# Cyber_VCM.net
KiCad netlist of a schematic drawn in Altium Designer
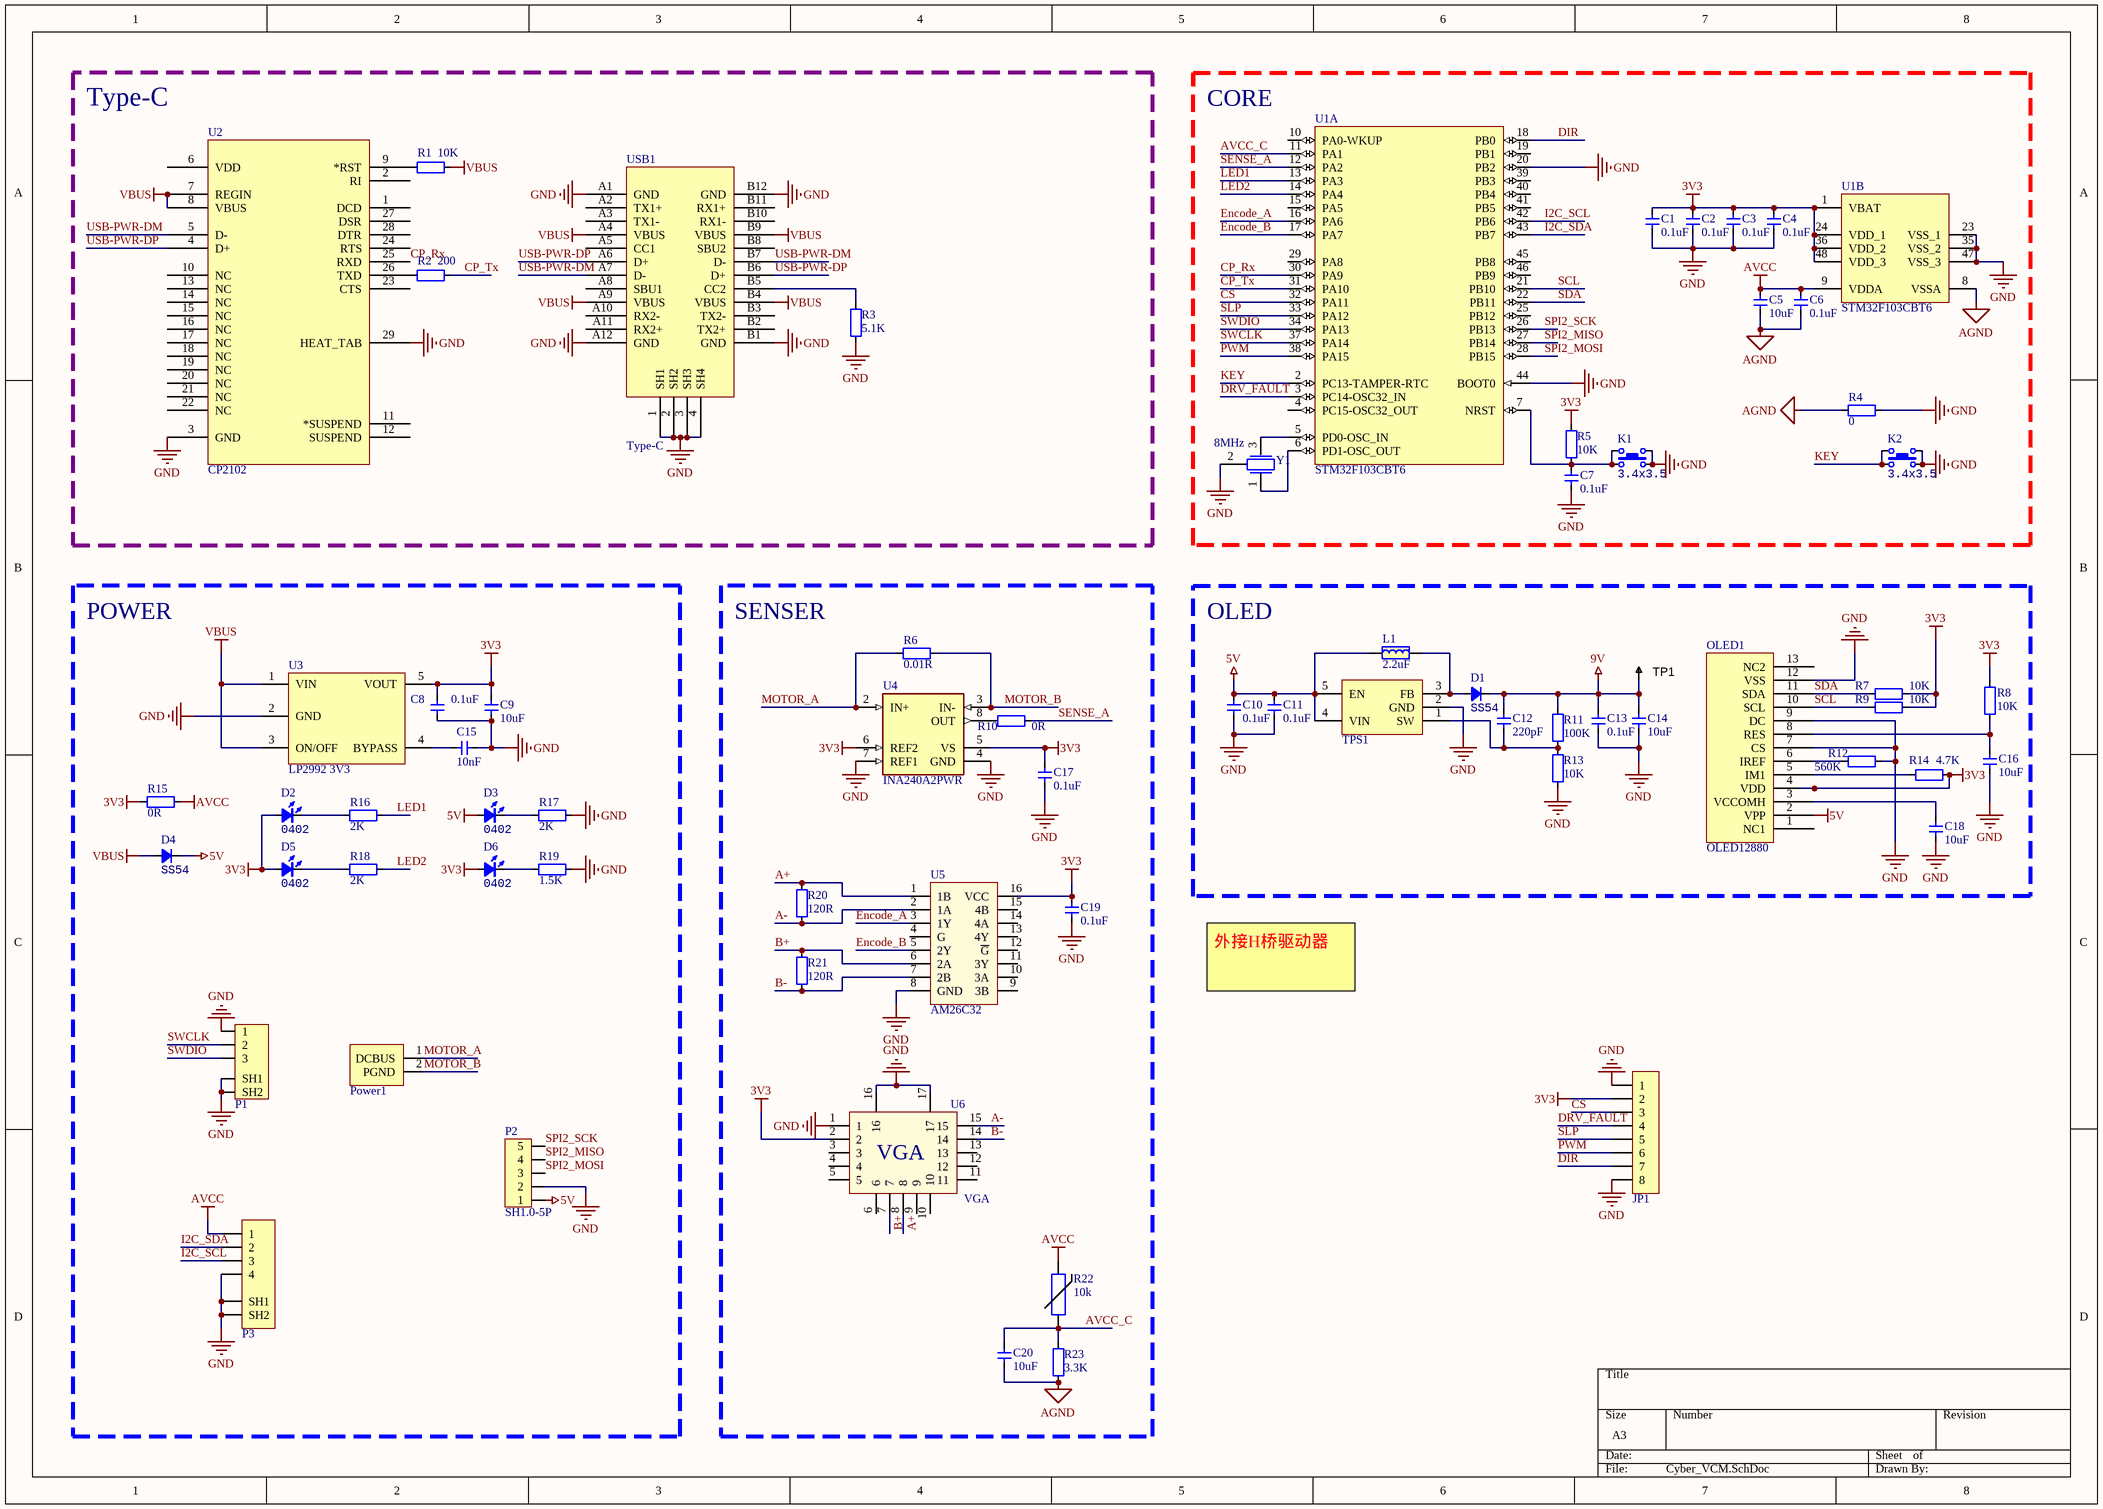
[diagram p0: Cyber_VCM.SchDoc]

(export (version "E")
  (design (tool "Eeschema 10.0.6"))
  (components
    (comp (ref "C1")
      (value "0.1uF")
      (footprint "CAP_0402")
      (description "Capacitor")
      (libsource (lib "Cyber_VCM") (part "电容-0402"))
    )
    (comp (ref "C2")
      (value "0.1uF")
      (footprint "CAP_0402")
      (description "Capacitor")
      (libsource (lib "Cyber_VCM") (part "电容-0402"))
    )
    (comp (ref "C3")
      (value "0.1uF")
      (footprint "CAP_0402")
      (description "Capacitor")
      (libsource (lib "Cyber_VCM") (part "电容-0402"))
    )
    (comp (ref "C4")
      (value "0.1uF")
      (footprint "CAP_0402")
      (description "Capacitor")
      (libsource (lib "Cyber_VCM") (part "电容-0402"))
    )
    (comp (ref "C5")
      (value "10uF")
      (footprint "CAP_0402")
      (description "Capacitor")
      (libsource (lib "Cyber_VCM") (part "电容-0402"))
    )
    (comp (ref "C6")
      (value "0.1uF")
      (footprint "CAP_0402")
      (description "Capacitor")
      (libsource (lib "Cyber_VCM") (part "电容-0402"))
    )
    (comp (ref "C7")
      (value "0.1uF")
      (footprint "CAP_0402")
      (description "Capacitor")
      (libsource (lib "MyPcbLib") (part "电容-0402"))
    )
    (comp (ref "C8")
      (value "0.1uF")
      (footprint "CAP_0402")
      (description "Capacitor")
      (libsource (lib "Cyber_VCM") (part "电容-0402"))
    )
    (comp (ref "C9")
      (value "10uF")
      (footprint "CAP_0402")
      (description "Capacitor")
      (libsource (lib "Cyber_VCM") (part "电容-0402"))
    )
    (comp (ref "C10")
      (value "0.1uF")
      (footprint "CAP_0402")
      (description "Capacitor")
      (libsource (lib "Serena-Ctrl") (part "电容-0402"))
    )
    (comp (ref "C11")
      (value "0.1uF")
      (footprint "CAP_0402")
      (description "Capacitor")
      (libsource (lib "Serena-Ctrl") (part "电容-0402"))
    )
    (comp (ref "C12")
      (value "220pF")
      (footprint "CAP_0402")
      (description "Capacitor")
      (libsource (lib "Serena-Ctrl") (part "电容-0402"))
    )
    (comp (ref "C13")
      (value "0.1uF")
      (footprint "0603-CAP")
      (description "Capacitor")
      (libsource (lib "Serena-Ctrl") (part "电容-0603"))
    )
    (comp (ref "C14")
      (value "10uF")
      (footprint "0603-CAP")
      (description "Capacitor")
      (libsource (lib "Serena-Ctrl") (part "电容-0603"))
    )
    (comp (ref "C15")
      (value "10nF")
      (footprint "CAP_0402")
      (description "Capacitor")
      (libsource (lib "Cyber_VCM") (part "电容-0402"))
    )
    (comp (ref "C16")
      (value "10uF")
      (footprint "CAP_0402")
      (description "Capacitor")
      (libsource (lib "MyPcbLib") (part "电容-0402"))
    )
    (comp (ref "C17")
      (value "0.1uF")
      (footprint "CAP_0402")
      (description "Capacitor")
      (libsource (lib "MyPcbLib") (part "电容-0402"))
    )
    (comp (ref "C18")
      (value "10uF")
      (footprint "CAP_0402")
      (description "Capacitor")
      (libsource (lib "MyPcbLib") (part "电容-0402"))
    )
    (comp (ref "C19")
      (value "0.1uF")
      (footprint "0603-CAP")
      (description "Capacitor")
      (libsource (lib "VCM_Ctrl") (part "电容-0603"))
    )
    (comp (ref "C20")
      (value "10uF")
      (footprint "CAP_0402")
      (description "Capacitor")
      (libsource (lib "MyPcbLib") (part "电容-0402"))
    )
    (comp (ref "D1")
      (value "SS54")
      (footprint "DO-214AC")
      (description "Diode")
      (libsource (lib "Serena-Ctrl") (part "Diode_SMA"))
    )
    (comp (ref "D2")
      (value "color?")
      (footprint "LED_0402_BLUE")
      (description "LED")
      (fields (field (name "TYPE") "0402"))
      (libsource (lib "Cyber_VCM") (part "LED_0402"))
    )
    (comp (ref "D3")
      (value "color?")
      (footprint "LED_0402_BLUE")
      (description "LED")
      (fields (field (name "TYPE") "0402"))
      (libsource (lib "Cyber_VCM") (part "LED_0402"))
    )
    (comp (ref "D4")
      (value "SS54")
      (footprint "DO-214AC")
      (description "Diode")
      (libsource (lib "Cyber_VCM") (part "Diode_SMA"))
    )
    (comp (ref "D5")
      (value "color?")
      (footprint "LED_0402_BLUE")
      (description "LED")
      (fields (field (name "TYPE") "0402"))
      (libsource (lib "Cyber_VCM") (part "LED_0402"))
    )
    (comp (ref "D6")
      (value "color?")
      (footprint "LED_0402_BLUE")
      (description "LED")
      (fields (field (name "TYPE") "0402"))
      (libsource (lib "Cyber_VCM") (part "LED_0402"))
    )
    (comp (ref "JP1")
      (value "HDR-1X8")
      (footprint "HDR2.54-M-LI-8P")
      (description "8P接插件")
      (fields (field (name "版权归属") "源创客"))
      (libsource (lib "Cyber_VCM") (part "Header 8"))
    )
    (comp (ref "K1")
      (value "3.4x3.5")
      (footprint "ButtonTACT_3.5*3.55_90")
      (description "Button")
      (fields (field (name "Comment") "TACT 4P"))
      (libsource (lib "KitSprout") (part "ButtonTACT"))
    )
    (comp (ref "K2")
      (value "3.4x3.5")
      (footprint "ButtonTACT_3.5*3.55_90")
      (description "Button")
      (fields (field (name "Comment") "TACT 4P"))
      (libsource (lib "KitSprout") (part "ButtonTACT"))
    )
    (comp (ref "L1")
      (value "2.2uF")
      (footprint "2520-L")
      (description "磁珠")
      (libsource (lib "Serena-Ctrl") (part "电感-0805"))
    )
    (comp (ref "OLED1")
      (value "OLED12880")
      (footprint "OLED12880")
      (description "12880寸OLED")
      (libsource (lib "Cyber_VCM") (part "OLED12880"))
    )
    (comp (ref "P1")
      (value "SH1.0-3P")
      (footprint "SH1.0-3P")
      (description "Header")
      (libsource (lib "Cyber_VCM") (part "SH1.0-3P"))
    )
    (comp (ref "P2") (value "SH1.0-5P") (footprint "SH1.0-5P") (libsource (lib "MyPcbLib") (part "SH1.0-5P")))
    (comp (ref "P3")
      (value "SH1.0-4P")
      (footprint "SH1.0-4P")
      (libsource (lib "Cyber_VCM") (part "SH1.0-4P"))
    )
    (comp (ref "Power1")
      (value "电源")
      (footprint "TX60电源")
      (description "12~24VDC电源")
      (libsource (lib "Cyber_VCM") (part "电源"))
    )
    (comp (ref "R1")
      (value "10K")
      (footprint "RES_0402")
      (description "Resistor")
      (libsource (lib "MyPcbLib") (part "电阻-0402"))
    )
    (comp (ref "R2")
      (value "200")
      (footprint "RES_0402")
      (description "Resistor")
      (libsource (lib "MyPcbLib") (part "电阻-0402"))
    )
    (comp (ref "R3")
      (value "5.1K")
      (footprint "RES_0402")
      (description "Resistor")
      (libsource (lib "") (part "电阻-0402_3"))
    )
    (comp (ref "R4")
      (value "0")
      (footprint "RES_0402")
      (description "Resistor")
      (libsource (lib "Cyber_VCM") (part "电阻-0402"))
    )
    (comp (ref "R5")
      (value "10K")
      (footprint "RES_0402")
      (description "Resistor")
      (libsource (lib "") (part "电阻-0402_1"))
    )
    (comp (ref "R6")
      (value "0.01R")
      (footprint "1206-RES")
      (description "Resistor")
      (libsource (lib "MyPcbLib") (part "电阻-1206"))
    )
    (comp (ref "R7")
      (value "10K")
      (footprint "RES_0402")
      (description "Resistor")
      (libsource (lib "VectorController") (part "电阻-0402"))
    )
    (comp (ref "R8")
      (value "10K")
      (footprint "RES_0402")
      (description "Resistor")
      (libsource (lib "") (part "电阻-0402_1"))
    )
    (comp (ref "R9")
      (value "10K")
      (footprint "RES_0402")
      (description "Resistor")
      (libsource (lib "VectorController") (part "电阻-0402"))
    )
    (comp (ref "R10")
      (value "0R")
      (footprint "RES_0402")
      (description "Resistor")
      (libsource (lib "Cyber_VCM") (part "电阻-0402"))
    )
    (comp (ref "R11")
      (value "100K")
      (footprint "RES_0402")
      (description "Resistor")
      (libsource (lib "Serena-Ctrl") (part "电阻-0402"))
    )
    (comp (ref "R12")
      (value "560K")
      (footprint "RES_0402")
      (description "Resistor")
      (libsource (lib "") (part "电阻-0402_2"))
    )
    (comp (ref "R13")
      (value "10K")
      (footprint "RES_0402")
      (description "Resistor")
      (libsource (lib "Serena-Ctrl") (part "电阻-0402"))
    )
    (comp (ref "R14")
      (value "4.7K")
      (footprint "RES_0402")
      (description "Resistor")
      (libsource (lib "") (part "电阻-0402_2"))
    )
    (comp (ref "R15")
      (value "0R")
      (footprint "RES_0402")
      (description "Resistor")
      (libsource (lib "MyPcbLib") (part "电阻-0402"))
    )
    (comp (ref "R16")
      (value "2K")
      (footprint "RES_0402")
      (description "Resistor")
      (libsource (lib "Cyber_VCM") (part "电阻-0402"))
    )
    (comp (ref "R17")
      (value "2K")
      (footprint "RES_0402")
      (description "Resistor")
      (libsource (lib "Cyber_VCM") (part "电阻-0402"))
    )
    (comp (ref "R18")
      (value "2K")
      (footprint "RES_0402")
      (description "Resistor")
      (libsource (lib "Cyber_VCM") (part "电阻-0402"))
    )
    (comp (ref "R19")
      (value "1.5K")
      (footprint "RES_0402")
      (description "Resistor")
      (libsource (lib "Cyber_VCM") (part "电阻-0402"))
    )
    (comp (ref "R20")
      (value "120R")
      (footprint "RES_0603")
      (description "Resistor")
      (libsource (lib "Ctrl_FOC") (part "电阻-0603"))
    )
    (comp (ref "R21")
      (value "120R")
      (footprint "RES_0603")
      (description "Resistor")
      (libsource (lib "Ctrl_FOC") (part "电阻-0603"))
    )
    (comp (ref "R22")
      (value "10k")
      (footprint "RES_0402")
      (description "THERMISTOR 10K OHM NTC 0402 SMD")
      (fields (field (name "Comment") "NCP15XH103F03RC"))
      (libsource (lib "MyPcbLib") (part "NCP15XH103F03RC"))
    )
    (comp (ref "R23")
      (value "3.3K")
      (footprint "RES_0402")
      (description "Resistor")
      (libsource (lib "") (part "电阻-0402_1"))
    )
    (comp (ref "TP1")
      (value "TESTPOINT")
      (footprint "TP-R30")
      (description "SMD test pin")
      (libsource (lib "Serena-Ctrl") (part "TESTPOINT"))
    )
    (comp (ref "TPS1")
      (value "TPS61040DBV")
      (footprint "SOT23-5")
      (libsource (lib "Serena-Ctrl") (part "TPS61040DBV"))
    )
    (comp (ref "U1")
      (value "STM32F103CBT6")
      (footprint "LQFP-48")
      (libsource (lib "Cyber_VCM") (part "STM32F103CBT6"))
    )
    (comp (ref "U2")
      (value "CP2102")
      (footprint "QFN-28")
      (description "USB转TTL")
      (libsource (lib "Cyber_VCM") (part "CP2102"))
    )
    (comp (ref "U3")
      (value "LP2992 3V3")
      (footprint "SOT23-5")
      (description "LDO")
      (libsource (lib "Cyber_VCM") (part "LP2992"))
    )
    (comp (ref "U4")
      (value "INA240A2PWR")
      (footprint "SOP65 P640X120-8N")
      (fields (field (name "MF") "Texas Instruments"))
      (libsource (lib "mLib") (part "INA240A2PWR"))
    )
    (comp (ref "U5")
      (value "AM26C32")
      (footprint "SOP16")
      (description "AM26C32 Quadruple Differential Line Receiver")
      (libsource (lib "VCM_Ctrl") (part "AM26C32"))
    )
    (comp (ref "U6") (value "VGA") (footprint "VGA15A") (libsource (lib "VCM_Ctrl") (part "VGA")))
    (comp (ref "USB1")
      (value "Type-C")
      (footprint "Type-C-TOP")
      (libsource (lib "Cyber_VCM") (part "USB-Type-C-TOP"))
    )
    (comp (ref "Y1")
      (value "8MHz")
      (footprint "晶振-3P")
      (description "村田贴片")
      (libsource (lib "MyPcbLib") (part "晶振-3Pin"))
    )
  )
  (nets
    (net (code "1") (name "/A+") (class "Default")
      (node (ref "R20") (pin "2") (pinfunction "2_2") (pintype "passive"))
      (node (ref "U5") (pin "1") (pinfunction "1B_1") (pintype "passive"))
      (node (ref "U6") (pin "8") (pinfunction "8_8") (pintype "passive"))
    )
    (net (code "2") (name "/A-") (class "Default")
      (node (ref "R20") (pin "1") (pinfunction "1_1") (pintype "passive"))
      (node (ref "U5") (pin "2") (pinfunction "1A_2") (pintype "passive"))
      (node (ref "U6") (pin "15") (pinfunction "15_15") (pintype "passive"))
    )
    (net (code "3") (name "/AVCC_C") (class "Default")
      (node (ref "C20") (pin "2") (pinfunction "2_2") (pintype "passive"))
      (node (ref "R22") (pin "1") (pinfunction "0_1") (pintype "passive"))
      (node (ref "R23") (pin "2") (pinfunction "2_2") (pintype "passive"))
      (node (ref "U1") (pin "11") (pinfunction "PA1_11") (pintype "bidirectional"))
    )
    (net (code "4") (name "/B+") (class "Default")
      (node (ref "R21") (pin "2") (pinfunction "2_2") (pintype "passive"))
      (node (ref "U5") (pin "6") (pinfunction "2A_6") (pintype "passive"))
      (node (ref "U6") (pin "7") (pinfunction "7_7") (pintype "passive"))
    )
    (net (code "5") (name "/B-") (class "Default")
      (node (ref "R21") (pin "1") (pinfunction "1_1") (pintype "passive"))
      (node (ref "U5") (pin "7") (pinfunction "2B_7") (pintype "passive"))
      (node (ref "U6") (pin "14") (pinfunction "14_14") (pintype "passive"))
    )
    (net (code "6") (name "/CP_Rx") (class "Default")
      (node (ref "U1") (pin "30") (pinfunction "PA9_30") (pintype "bidirectional"))
      (node (ref "U2") (pin "25") (pinfunction "RXD_25") (pintype "passive"))
    )
    (net (code "7") (name "/CP_Tx") (class "Default")
      (node (ref "R2") (pin "1") (pinfunction "1_1") (pintype "passive"))
      (node (ref "U1") (pin "31") (pinfunction "PA10_31") (pintype "bidirectional"))
    )
    (net (code "8") (name "/CS") (class "Default")
      (node (ref "JP1") (pin "3") (pinfunction "3_3") (pintype "passive"))
      (node (ref "U1") (pin "32") (pinfunction "PA11_32") (pintype "bidirectional"))
    )
    (net (code "9") (name "/DIR") (class "Default")
      (node (ref "JP1") (pin "7") (pinfunction "7_7") (pintype "passive"))
      (node (ref "U1") (pin "18") (pinfunction "PB0_18") (pintype "bidirectional"))
    )
    (net (code "10") (name "/DRV_FAULT") (class "Default")
      (node (ref "JP1") (pin "4") (pinfunction "4_4") (pintype "passive"))
      (node (ref "U1") (pin "3") (pinfunction "PC14-OSC32_IN_3") (pintype "bidirectional"))
    )
    (net (code "11") (name "/Encode_A") (class "Default")
      (node (ref "U1") (pin "16") (pinfunction "PA6_16") (pintype "bidirectional"))
      (node (ref "U5") (pin "3") (pinfunction "1Y_3") (pintype "passive"))
    )
    (net (code "12") (name "/Encode_B") (class "Default")
      (node (ref "U1") (pin "17") (pinfunction "PA7_17") (pintype "bidirectional"))
      (node (ref "U5") (pin "5") (pinfunction "2Y_5") (pintype "passive"))
    )
    (net (code "13") (name "/I2C_SCL") (class "Default")
      (node (ref "P3") (pin "3") (pinfunction "3_3") (pintype "passive"))
      (node (ref "U1") (pin "42") (pinfunction "PB6_42") (pintype "bidirectional"))
    )
    (net (code "14") (name "/I2C_SDA") (class "Default")
      (node (ref "P3") (pin "2") (pinfunction "2_2") (pintype "passive"))
      (node (ref "U1") (pin "43") (pinfunction "PB7_43") (pintype "bidirectional"))
    )
    (net (code "15") (name "/KEY") (class "Default")
      (node (ref "K2") (pin "1") (pinfunction "1_1") (pintype "passive"))
      (node (ref "K2") (pin "3") (pinfunction "3_3") (pintype "passive"))
      (node (ref "U1") (pin "2") (pinfunction "PC13-TAMPER-RTC_2") (pintype "bidirectional"))
    )
    (net (code "16") (name "/LED1") (class "Default")
      (node (ref "R16") (pin "2") (pinfunction "2_2") (pintype "passive"))
      (node (ref "U1") (pin "13") (pinfunction "PA3_13") (pintype "bidirectional"))
    )
    (net (code "17") (name "/LED2") (class "Default")
      (node (ref "R18") (pin "2") (pinfunction "2_2") (pintype "passive"))
      (node (ref "U1") (pin "14") (pinfunction "PA4_14") (pintype "bidirectional"))
    )
    (net (code "18") (name "/MOTOR_A") (class "Default")
      (node (ref "Power1") (pin "1") (pinfunction "DCBUS_1") (pintype "passive"))
      (node (ref "R6") (pin "1") (pinfunction "1_1") (pintype "passive"))
      (node (ref "U4") (pin "2") (pinfunction "IN+_2") (pintype "input"))
    )
    (net (code "19") (name "/MOTOR_B") (class "Default")
      (node (ref "Power1") (pin "2") (pinfunction "PGND_2") (pintype "passive"))
      (node (ref "R6") (pin "2") (pinfunction "2_2") (pintype "passive"))
      (node (ref "U4") (pin "3") (pinfunction "IN-_3") (pintype "input"))
    )
    (net (code "20") (name "/PWM") (class "Default")
      (node (ref "JP1") (pin "6") (pinfunction "6_6") (pintype "passive"))
      (node (ref "U1") (pin "38") (pinfunction "PA15_38") (pintype "bidirectional"))
    )
    (net (code "21") (name "/SCL") (class "Default")
      (node (ref "OLED1") (pin "10") (pinfunction "SCL_10") (pintype "passive"))
      (node (ref "R9") (pin "1") (pinfunction "1_1") (pintype "passive"))
      (node (ref "U1") (pin "21") (pinfunction "PB10_21") (pintype "bidirectional"))
    )
    (net (code "22") (name "/SDA") (class "Default")
      (node (ref "OLED1") (pin "11") (pinfunction "SDA_11") (pintype "passive"))
      (node (ref "R7") (pin "1") (pinfunction "1_1") (pintype "passive"))
      (node (ref "U1") (pin "22") (pinfunction "PB11_22") (pintype "bidirectional"))
    )
    (net (code "23") (name "/SENSE_A") (class "Default")
      (node (ref "R10") (pin "2") (pinfunction "2_2") (pintype "passive"))
      (node (ref "U1") (pin "12") (pinfunction "PA2_12") (pintype "bidirectional"))
    )
    (net (code "24") (name "/SLP") (class "Default")
      (node (ref "JP1") (pin "5") (pinfunction "5_5") (pintype "passive"))
      (node (ref "U1") (pin "33") (pinfunction "PA12_33") (pintype "bidirectional"))
    )
    (net (code "25") (name "/SPI2_MISO") (class "Default")
      (node (ref "P2") (pin "4") (pinfunction "4_4") (pintype "passive"))
      (node (ref "U1") (pin "27") (pinfunction "PB14_27") (pintype "bidirectional"))
    )
    (net (code "26") (name "/SPI2_MOSI") (class "Default")
      (node (ref "P2") (pin "3") (pinfunction "3_3") (pintype "passive"))
      (node (ref "U1") (pin "28") (pinfunction "PB15_28") (pintype "bidirectional"))
    )
    (net (code "27") (name "/SPI2_SCK") (class "Default")
      (node (ref "P2") (pin "5") (pinfunction "5_5") (pintype "passive"))
      (node (ref "U1") (pin "26") (pinfunction "PB13_26") (pintype "bidirectional"))
    )
    (net (code "28") (name "/SWCLK") (class "Default")
      (node (ref "P1") (pin "2") (pinfunction "2_2") (pintype "passive"))
      (node (ref "U1") (pin "37") (pinfunction "PA14_37") (pintype "bidirectional"))
    )
    (net (code "29") (name "/SWDIO") (class "Default")
      (node (ref "P1") (pin "3") (pinfunction "3_3") (pintype "passive"))
      (node (ref "U1") (pin "34") (pinfunction "PA13_34") (pintype "bidirectional"))
    )
    (net (code "30") (name "/USB-PWR-DM") (class "Default")
      (node (ref "U2") (pin "5") (pinfunction "D-_5") (pintype "passive"))
      (node (ref "USB1") (pin "A7") (pinfunction "D-_A7") (pintype "passive"))
      (node (ref "USB1") (pin "B7") (pinfunction "D-_B7") (pintype "passive"))
    )
    (net (code "31") (name "/USB-PWR-DP") (class "Default")
      (node (ref "U2") (pin "4") (pinfunction "D+_4") (pintype "passive"))
      (node (ref "USB1") (pin "A6") (pinfunction "D+_A6") (pintype "passive"))
      (node (ref "USB1") (pin "B6") (pinfunction "D+_B6") (pintype "passive"))
    )
    (net (code "32") (name "3V3") (class "Default")
      (node (ref "C1") (pin "2") (pinfunction "2_2") (pintype "passive"))
      (node (ref "C17") (pin "2") (pinfunction "2_2") (pintype "passive"))
      (node (ref "C19") (pin "2") (pinfunction "2_2") (pintype "passive"))
      (node (ref "C2") (pin "2") (pinfunction "2_2") (pintype "passive"))
      (node (ref "C3") (pin "2") (pinfunction "2_2") (pintype "passive"))
      (node (ref "C4") (pin "2") (pinfunction "2_2") (pintype "passive"))
      (node (ref "C8") (pin "2") (pinfunction "2_2") (pintype "passive"))
      (node (ref "C9") (pin "2") (pinfunction "2_2") (pintype "passive"))
      (node (ref "D2") (pin "1") (pinfunction "A_1") (pintype "passive"))
      (node (ref "D5") (pin "1") (pinfunction "A_1") (pintype "passive"))
      (node (ref "D6") (pin "1") (pinfunction "A_1") (pintype "passive"))
      (node (ref "JP1") (pin "2") (pinfunction "2_2") (pintype "passive"))
      (node (ref "OLED1") (pin "4") (pinfunction "VDD_4") (pintype "passive"))
      (node (ref "R14") (pin "2") (pinfunction "2_2") (pintype "passive"))
      (node (ref "R15") (pin "2") (pinfunction "2_2") (pintype "passive"))
      (node (ref "R5") (pin "2") (pinfunction "2_2") (pintype "passive"))
      (node (ref "R7") (pin "2") (pinfunction "2_2") (pintype "passive"))
      (node (ref "R8") (pin "2") (pinfunction "2_2") (pintype "passive"))
      (node (ref "R9") (pin "2") (pinfunction "2_2") (pintype "passive"))
      (node (ref "U1") (pin "1") (pinfunction "VBAT_1") (pintype "power_in"))
      (node (ref "U1") (pin "24") (pinfunction "VDD_1_24") (pintype "power_in"))
      (node (ref "U1") (pin "36") (pinfunction "VDD_2_36") (pintype "power_in"))
      (node (ref "U1") (pin "48") (pinfunction "VDD_3_48") (pintype "power_in"))
      (node (ref "U3") (pin "5") (pinfunction "VOUT_5") (pintype "passive"))
      (node (ref "U4") (pin "5") (pinfunction "VS_5") (pintype "power_in"))
      (node (ref "U4") (pin "6") (pinfunction "REF2_6") (pintype "input"))
      (node (ref "U5") (pin "16") (pinfunction "VCC_16") (pintype "passive"))
      (node (ref "U6") (pin "2") (pinfunction "2_2") (pintype "passive"))
    )
    (net (code "33") (name "5V") (class "Default")
      (node (ref "C10") (pin "2") (pinfunction "2_2") (pintype "passive"))
      (node (ref "C11") (pin "2") (pinfunction "2_2") (pintype "passive"))
      (node (ref "D3") (pin "1") (pinfunction "A_1") (pintype "passive"))
      (node (ref "D4") (pin "2") (pinfunction "K_2") (pintype "passive"))
      (node (ref "L1") (pin "1") (pintype "passive"))
      (node (ref "OLED1") (pin "2") (pinfunction "VPP_2") (pintype "passive"))
      (node (ref "P2") (pin "1") (pinfunction "1_1") (pintype "passive"))
      (node (ref "TPS1") (pin "4") (pinfunction "VIN_4") (pintype "passive"))
      (node (ref "TPS1") (pin "5") (pinfunction "EN_5") (pintype "passive"))
    )
    (net (code "34") (name "9V") (class "Default")
      (node (ref "C12") (pin "2") (pinfunction "2_2") (pintype "passive"))
      (node (ref "C13") (pin "2") (pinfunction "2_2") (pintype "passive"))
      (node (ref "C14") (pin "2") (pinfunction "2_2") (pintype "passive"))
      (node (ref "D1") (pin "2") (pinfunction "K_2") (pintype "passive"))
      (node (ref "R11") (pin "2") (pinfunction "2_2") (pintype "passive"))
      (node (ref "TP1") (pin "1") (pintype "passive"))
    )
    (net (code "35") (name "AGND") (class "Default")
      (node (ref "C20") (pin "1") (pinfunction "1_1") (pintype "passive"))
      (node (ref "C5") (pin "1") (pinfunction "1_1") (pintype "passive"))
      (node (ref "C6") (pin "1") (pinfunction "1_1") (pintype "passive"))
      (node (ref "R23") (pin "1") (pinfunction "1_1") (pintype "passive"))
      (node (ref "R4") (pin "1") (pinfunction "1_1") (pintype "passive"))
      (node (ref "U1") (pin "8") (pinfunction "VSSA_8") (pintype "power_in"))
    )
    (net (code "36") (name "AVCC") (class "Default")
      (node (ref "C5") (pin "2") (pinfunction "2_2") (pintype "passive"))
      (node (ref "C6") (pin "2") (pinfunction "2_2") (pintype "passive"))
      (node (ref "P3") (pin "1") (pinfunction "1_1") (pintype "passive"))
      (node (ref "R15") (pin "1") (pinfunction "1_1") (pintype "passive"))
      (node (ref "R22") (pin "2") (pinfunction "0_2") (pintype "passive"))
      (node (ref "U1") (pin "9") (pinfunction "VDDA_9") (pintype "power_in"))
    )
    (net (code "37") (name "GND") (class "Default")
      (node (ref "C1") (pin "1") (pinfunction "1_1") (pintype "passive"))
      (node (ref "C10") (pin "1") (pinfunction "1_1") (pintype "passive"))
      (node (ref "C11") (pin "1") (pinfunction "1_1") (pintype "passive"))
      (node (ref "C13") (pin "1") (pinfunction "1_1") (pintype "passive"))
      (node (ref "C14") (pin "1") (pinfunction "1_1") (pintype "passive"))
      (node (ref "C15") (pin "2") (pinfunction "2_2") (pintype "passive"))
      (node (ref "C16") (pin "1") (pinfunction "1_1") (pintype "passive"))
      (node (ref "C17") (pin "1") (pinfunction "1_1") (pintype "passive"))
      (node (ref "C18") (pin "1") (pinfunction "1_1") (pintype "passive"))
      (node (ref "C19") (pin "1") (pinfunction "1_1") (pintype "passive"))
      (node (ref "C2") (pin "1") (pinfunction "1_1") (pintype "passive"))
      (node (ref "C3") (pin "1") (pinfunction "1_1") (pintype "passive"))
      (node (ref "C4") (pin "1") (pinfunction "1_1") (pintype "passive"))
      (node (ref "C7") (pin "1") (pinfunction "1_1") (pintype "passive"))
      (node (ref "C8") (pin "1") (pinfunction "1_1") (pintype "passive"))
      (node (ref "C9") (pin "1") (pinfunction "1_1") (pintype "passive"))
      (node (ref "JP1") (pin "1") (pinfunction "1_1") (pintype "passive"))
      (node (ref "JP1") (pin "8") (pinfunction "8_8") (pintype "passive"))
      (node (ref "K1") (pin "2") (pinfunction "2_2") (pintype "passive"))
      (node (ref "K1") (pin "4") (pinfunction "4_4") (pintype "passive"))
      (node (ref "K2") (pin "2") (pinfunction "2_2") (pintype "passive"))
      (node (ref "K2") (pin "4") (pinfunction "4_4") (pintype "passive"))
      (node (ref "OLED1") (pin "12") (pinfunction "VSS_12") (pintype "passive"))
      (node (ref "OLED1") (pin "7") (pinfunction "CS_7") (pintype "passive"))
      (node (ref "OLED1") (pin "9") (pinfunction "DC_9") (pintype "passive"))
      (node (ref "P1") (pin "1") (pinfunction "1_1") (pintype "passive"))
      (node (ref "P1") (pin "SH1") (pinfunction "SH1_SH1") (pintype "passive"))
      (node (ref "P1") (pin "SH2") (pinfunction "SH2_SH2") (pintype "passive"))
      (node (ref "P2") (pin "2") (pinfunction "2_2") (pintype "passive"))
      (node (ref "P3") (pin "4") (pinfunction "4_4") (pintype "passive"))
      (node (ref "P3") (pin "SH1") (pinfunction "SH1_SH1") (pintype "passive"))
      (node (ref "P3") (pin "SH2") (pinfunction "SH2_SH2") (pintype "passive"))
      (node (ref "R12") (pin "2") (pinfunction "2_2") (pintype "passive"))
      (node (ref "R13") (pin "1") (pinfunction "1_1") (pintype "passive"))
      (node (ref "R17") (pin "2") (pinfunction "2_2") (pintype "passive"))
      (node (ref "R19") (pin "2") (pinfunction "2_2") (pintype "passive"))
      (node (ref "R3") (pin "2") (pinfunction "2_2") (pintype "passive"))
      (node (ref "R4") (pin "2") (pinfunction "2_2") (pintype "passive"))
      (node (ref "TPS1") (pin "2") (pinfunction "GND_2") (pintype "passive"))
      (node (ref "U1") (pin "20") (pinfunction "PB2_20") (pintype "bidirectional"))
      (node (ref "U1") (pin "23") (pinfunction "VSS_1_23") (pintype "power_in"))
      (node (ref "U1") (pin "35") (pinfunction "VSS_2_35") (pintype "power_in"))
      (node (ref "U1") (pin "44") (pinfunction "BOOT0_44") (pintype "input"))
      (node (ref "U1") (pin "47") (pinfunction "VSS_3_47") (pintype "power_in"))
      (node (ref "U2") (pin "29") (pinfunction "HEAT_TAB_29") (pintype "passive"))
      (node (ref "U2") (pin "3") (pinfunction "GND_3") (pintype "passive"))
      (node (ref "U3") (pin "2") (pinfunction "GND_2") (pintype "passive"))
      (node (ref "U4") (pin "4") (pinfunction "GND_4") (pintype "power_in"))
      (node (ref "U4") (pin "7") (pinfunction "REF1_7") (pintype "input"))
      (node (ref "U5") (pin "8") (pinfunction "GND_8") (pintype "passive"))
      (node (ref "U6") (pin "1") (pinfunction "1_1") (pintype "passive"))
      (node (ref "U6") (pin "16") (pinfunction "16_16") (pintype "passive"))
      (node (ref "U6") (pin "17") (pinfunction "17_17") (pintype "passive"))
      (node (ref "USB1") (pin "1") (pinfunction "SH1_1") (pintype "passive"))
      (node (ref "USB1") (pin "2") (pinfunction "SH2_2") (pintype "passive"))
      (node (ref "USB1") (pin "3") (pinfunction "SH3_3") (pintype "passive"))
      (node (ref "USB1") (pin "4") (pinfunction "SH4_4") (pintype "passive"))
      (node (ref "USB1") (pin "A1") (pinfunction "GND_A1") (pintype "passive"))
      (node (ref "USB1") (pin "A12") (pinfunction "GND_A12") (pintype "passive"))
      (node (ref "USB1") (pin "B1") (pinfunction "GND_B1") (pintype "passive"))
      (node (ref "USB1") (pin "B12") (pinfunction "GND_B12") (pintype "passive"))
      (node (ref "Y1") (pin "2") (pinfunction "2_2") (pintype "passive"))
    )
    (net (code "38") (name "Net-(D1-A)") (class "Default")
      (node (ref "D1") (pin "1") (pinfunction "A_1") (pintype "passive"))
      (node (ref "L1") (pin "2") (pinfunction "2_2") (pintype "passive"))
      (node (ref "TPS1") (pin "3") (pinfunction "FB_3") (pintype "passive"))
    )
    (net (code "39") (name "Net-(D2-K)") (class "Default")
      (node (ref "D2") (pin "2") (pinfunction "K_2") (pintype "passive"))
      (node (ref "R16") (pin "1") (pinfunction "1_1") (pintype "passive"))
    )
    (net (code "40") (name "Net-(D3-K)") (class "Default")
      (node (ref "D3") (pin "2") (pinfunction "K_2") (pintype "passive"))
      (node (ref "R17") (pin "1") (pinfunction "1_1") (pintype "passive"))
    )
    (net (code "41") (name "Net-(D5-K)") (class "Default")
      (node (ref "D5") (pin "2") (pinfunction "K_2") (pintype "passive"))
      (node (ref "R18") (pin "1") (pinfunction "1_1") (pintype "passive"))
    )
    (net (code "42") (name "Net-(D6-K)") (class "Default")
      (node (ref "D6") (pin "2") (pinfunction "K_2") (pintype "passive"))
      (node (ref "R19") (pin "1") (pinfunction "1_1") (pintype "passive"))
    )
    (net (code "43") (name "Net-(OLED1-IM1)") (class "Default")
      (node (ref "OLED1") (pin "5") (pinfunction "IM1_5") (pintype "passive"))
      (node (ref "R14") (pin "1") (pinfunction "1_1") (pintype "passive"))
    )
    (net (code "44") (name "Net-(OLED1-IREF)") (class "Default")
      (node (ref "OLED1") (pin "6") (pinfunction "IREF_6") (pintype "passive"))
      (node (ref "R12") (pin "1") (pinfunction "1_1") (pintype "passive"))
    )
    (net (code "45") (name "Net-(OLED1-RES)") (class "Default")
      (node (ref "C16") (pin "2") (pinfunction "2_2") (pintype "passive"))
      (node (ref "OLED1") (pin "8") (pinfunction "RES_8") (pintype "passive"))
      (node (ref "R8") (pin "1") (pinfunction "1_1") (pintype "passive"))
    )
    (net (code "46") (name "Net-(OLED1-VCCOMH)") (class "Default")
      (node (ref "C18") (pin "2") (pinfunction "2_2") (pintype "passive"))
      (node (ref "OLED1") (pin "3") (pinfunction "VCCOMH_3") (pintype "passive"))
    )
    (net (code "47") (name "Net-(TPS1-SW)") (class "Default")
      (node (ref "C12") (pin "1") (pinfunction "1_1") (pintype "passive"))
      (node (ref "R11") (pin "1") (pinfunction "1_1") (pintype "passive"))
      (node (ref "R13") (pin "2") (pinfunction "2_2") (pintype "passive"))
      (node (ref "TPS1") (pin "1") (pinfunction "SW_1") (pintype "passive"))
    )
    (net (code "48") (name "Net-(U1A-NRST)") (class "Default")
      (node (ref "C7") (pin "2") (pinfunction "2_2") (pintype "passive"))
      (node (ref "K1") (pin "1") (pinfunction "1_1") (pintype "passive"))
      (node (ref "K1") (pin "3") (pinfunction "3_3") (pintype "passive"))
      (node (ref "R5") (pin "1") (pinfunction "1_1") (pintype "passive"))
      (node (ref "U1") (pin "7") (pinfunction "NRST_7") (pintype "bidirectional"))
    )
    (net (code "49") (name "Net-(U1A-PD0-OSC_IN)") (class "Default")
      (node (ref "U1") (pin "5") (pinfunction "PD0-OSC_IN_5") (pintype "bidirectional"))
      (node (ref "Y1") (pin "3") (pinfunction "3_3") (pintype "passive"))
    )
    (net (code "50") (name "Net-(U1A-PD1-OSC_OUT)") (class "Default")
      (node (ref "U1") (pin "6") (pinfunction "PD1-OSC_OUT_6") (pintype "bidirectional"))
      (node (ref "Y1") (pin "1") (pinfunction "1_1") (pintype "passive"))
    )
    (net (code "51") (name "Net-(U2-*RST)") (class "Default")
      (node (ref "R1") (pin "2") (pinfunction "2_2") (pintype "passive"))
      (node (ref "U2") (pin "9") (pinfunction "*RST_9") (pintype "passive"))
    )
    (net (code "52") (name "Net-(U2-TXD)") (class "Default")
      (node (ref "R2") (pin "2") (pinfunction "2_2") (pintype "passive"))
      (node (ref "U2") (pin "26") (pinfunction "TXD_26") (pintype "passive"))
    )
    (net (code "53") (name "Net-(U3-BYPASS)") (class "Default")
      (node (ref "C15") (pin "1") (pinfunction "1_1") (pintype "passive"))
      (node (ref "U3") (pin "4") (pinfunction "BYPASS_4") (pintype "passive"))
    )
    (net (code "54") (name "Net-(U4-OUT)") (class "Default")
      (node (ref "R10") (pin "1") (pinfunction "1_1") (pintype "passive"))
      (node (ref "U4") (pin "8") (pinfunction "OUT_8") (pintype "output"))
    )
    (net (code "55") (name "Net-(USB1-CC2)") (class "Default")
      (node (ref "R3") (pin "1") (pinfunction "1_1") (pintype "passive"))
      (node (ref "USB1") (pin "B5") (pinfunction "CC2_B5") (pintype "passive"))
    )
    (net (code "56") (name "VBUS") (class "Default")
      (node (ref "D4") (pin "1") (pinfunction "A_1") (pintype "passive"))
      (node (ref "R1") (pin "1") (pinfunction "1_1") (pintype "passive"))
      (node (ref "U2") (pin "7") (pinfunction "REGIN_7") (pintype "passive"))
      (node (ref "U2") (pin "8") (pinfunction "VBUS_8") (pintype "passive"))
      (node (ref "U3") (pin "1") (pinfunction "VIN_1") (pintype "passive"))
      (node (ref "U3") (pin "3") (pinfunction "ON/OFF_3") (pintype "passive"))
      (node (ref "USB1") (pin "A4") (pinfunction "VBUS_A4") (pintype "passive"))
      (node (ref "USB1") (pin "A9") (pinfunction "VBUS_A9") (pintype "passive"))
      (node (ref "USB1") (pin "B4") (pinfunction "VBUS_B4") (pintype "passive"))
      (node (ref "USB1") (pin "B9") (pinfunction "VBUS_B9") (pintype "passive"))
    )
    (net (code "57") (name "unconnected-(OLED1-NC1-Pad1)") (class "Default")
      (node (ref "OLED1") (pin "1") (pinfunction "NC1_1") (pintype "passive"))
    )
    (net (code "58") (name "unconnected-(OLED1-NC2-Pad13)") (class "Default")
      (node (ref "OLED1") (pin "13") (pinfunction "NC2_13") (pintype "passive"))
    )
    (net (code "59") (name "unconnected-(U1A-PA0-WKUP-Pad10)") (class "Default")
      (node (ref "U1") (pin "10") (pinfunction "PA0-WKUP_10") (pintype "bidirectional"))
    )
    (net (code "60") (name "unconnected-(U1A-PA5-Pad15)") (class "Default")
      (node (ref "U1") (pin "15") (pinfunction "PA5_15") (pintype "bidirectional"))
    )
    (net (code "61") (name "unconnected-(U1A-PA8-Pad29)") (class "Default")
      (node (ref "U1") (pin "29") (pinfunction "PA8_29") (pintype "bidirectional"))
    )
    (net (code "62") (name "unconnected-(U1A-PB1-Pad19)") (class "Default")
      (node (ref "U1") (pin "19") (pinfunction "PB1_19") (pintype "bidirectional"))
    )
    (net (code "63") (name "unconnected-(U1A-PB3-Pad39)") (class "Default")
      (node (ref "U1") (pin "39") (pinfunction "PB3_39") (pintype "bidirectional"))
    )
    (net (code "64") (name "unconnected-(U1A-PB4-Pad40)") (class "Default")
      (node (ref "U1") (pin "40") (pinfunction "PB4_40") (pintype "bidirectional"))
    )
    (net (code "65") (name "unconnected-(U1A-PB5-Pad41)") (class "Default")
      (node (ref "U1") (pin "41") (pinfunction "PB5_41") (pintype "bidirectional"))
    )
    (net (code "66") (name "unconnected-(U1A-PB8-Pad45)") (class "Default")
      (node (ref "U1") (pin "45") (pinfunction "PB8_45") (pintype "bidirectional"))
    )
    (net (code "67") (name "unconnected-(U1A-PB9-Pad46)") (class "Default")
      (node (ref "U1") (pin "46") (pinfunction "PB9_46") (pintype "bidirectional"))
    )
    (net (code "68") (name "unconnected-(U1A-PB12-Pad25)") (class "Default")
      (node (ref "U1") (pin "25") (pinfunction "PB12_25") (pintype "bidirectional"))
    )
    (net (code "69") (name "unconnected-(U1A-PC15-OSC32_OUT-Pad4)") (class "Default")
      (node (ref "U1") (pin "4") (pinfunction "PC15-OSC32_OUT_4") (pintype "bidirectional"))
    )
    (net (code "70") (name "unconnected-(U2-*SUSPEND-Pad11)") (class "Default")
      (node (ref "U2") (pin "11") (pinfunction "*SUSPEND_11") (pintype "passive"))
    )
    (net (code "71") (name "unconnected-(U2-CTS-Pad23)") (class "Default")
      (node (ref "U2") (pin "23") (pinfunction "CTS_23") (pintype "passive"))
    )
    (net (code "72") (name "unconnected-(U2-DCD-Pad1)") (class "Default")
      (node (ref "U2") (pin "1") (pinfunction "DCD_1") (pintype "passive"))
    )
    (net (code "73") (name "unconnected-(U2-DSR-Pad27)") (class "Default")
      (node (ref "U2") (pin "27") (pinfunction "DSR_27") (pintype "passive"))
    )
    (net (code "74") (name "unconnected-(U2-DTR-Pad28)") (class "Default")
      (node (ref "U2") (pin "28") (pinfunction "DTR_28") (pintype "passive"))
    )
    (net (code "75") (name "unconnected-(U2-NC-Pad10)") (class "Default")
      (node (ref "U2") (pin "10") (pinfunction "NC_10") (pintype "passive"))
    )
    (net (code "76") (name "unconnected-(U2-NC-Pad13)") (class "Default")
      (node (ref "U2") (pin "13") (pinfunction "NC_13") (pintype "passive"))
    )
    (net (code "77") (name "unconnected-(U2-NC-Pad14)") (class "Default")
      (node (ref "U2") (pin "14") (pinfunction "NC_14") (pintype "passive"))
    )
    (net (code "78") (name "unconnected-(U2-NC-Pad15)") (class "Default")
      (node (ref "U2") (pin "15") (pinfunction "NC_15") (pintype "passive"))
    )
    (net (code "79") (name "unconnected-(U2-NC-Pad16)") (class "Default")
      (node (ref "U2") (pin "16") (pinfunction "NC_16") (pintype "passive"))
    )
    (net (code "80") (name "unconnected-(U2-NC-Pad17)") (class "Default")
      (node (ref "U2") (pin "17") (pinfunction "NC_17") (pintype "passive"))
    )
    (net (code "81") (name "unconnected-(U2-NC-Pad18)") (class "Default")
      (node (ref "U2") (pin "18") (pinfunction "NC_18") (pintype "passive"))
    )
    (net (code "82") (name "unconnected-(U2-NC-Pad19)") (class "Default")
      (node (ref "U2") (pin "19") (pinfunction "NC_19") (pintype "passive"))
    )
    (net (code "83") (name "unconnected-(U2-NC-Pad20)") (class "Default")
      (node (ref "U2") (pin "20") (pinfunction "NC_20") (pintype "passive"))
    )
    (net (code "84") (name "unconnected-(U2-NC-Pad21)") (class "Default")
      (node (ref "U2") (pin "21") (pinfunction "NC_21") (pintype "passive"))
    )
    (net (code "85") (name "unconnected-(U2-NC-Pad22)") (class "Default")
      (node (ref "U2") (pin "22") (pinfunction "NC_22") (pintype "passive"))
    )
    (net (code "86") (name "unconnected-(U2-RI-Pad2)") (class "Default")
      (node (ref "U2") (pin "2") (pinfunction "RI_2") (pintype "passive"))
    )
    (net (code "87") (name "unconnected-(U2-RTS-Pad24)") (class "Default")
      (node (ref "U2") (pin "24") (pinfunction "RTS_24") (pintype "passive"))
    )
    (net (code "88") (name "unconnected-(U2-SUSPEND-Pad12)") (class "Default")
      (node (ref "U2") (pin "12") (pinfunction "SUSPEND_12") (pintype "passive"))
    )
    (net (code "89") (name "unconnected-(U2-VDD-Pad6)") (class "Default")
      (node (ref "U2") (pin "6") (pinfunction "VDD_6") (pintype "passive"))
    )
    (net (code "90") (name "unconnected-(U5-3A-Pad10)") (class "Default")
      (node (ref "U5") (pin "10") (pinfunction "3A_10") (pintype "passive"))
    )
    (net (code "91") (name "unconnected-(U5-3B-Pad9)") (class "Default")
      (node (ref "U5") (pin "9") (pinfunction "3B_9") (pintype "passive"))
    )
    (net (code "92") (name "unconnected-(U5-3Y-Pad11)") (class "Default")
      (node (ref "U5") (pin "11") (pinfunction "3Y_11") (pintype "passive"))
    )
    (net (code "93") (name "unconnected-(U5-4A-Pad14)") (class "Default")
      (node (ref "U5") (pin "14") (pinfunction "4A_14") (pintype "passive"))
    )
    (net (code "94") (name "unconnected-(U5-4B-Pad15)") (class "Default")
      (node (ref "U5") (pin "15") (pinfunction "4B_15") (pintype "passive"))
    )
    (net (code "95") (name "unconnected-(U5-4Y-Pad13)") (class "Default")
      (node (ref "U5") (pin "13") (pinfunction "4Y_13") (pintype "passive"))
    )
    (net (code "96") (name "unconnected-(U5-G-Pad4)") (class "Default")
      (node (ref "U5") (pin "4") (pinfunction "G_4") (pintype "passive"))
    )
    (net (code "97") (name "unconnected-(U5-~{G}-Pad12)") (class "Default")
      (node (ref "U5") (pin "12") (pinfunction "~{G}_12") (pintype "passive"))
    )
    (net (code "98") (name "unconnected-(U6-Pad3)") (class "Default")
      (node (ref "U6") (pin "3") (pinfunction "3_3") (pintype "passive"))
    )
    (net (code "99") (name "unconnected-(U6-Pad4)") (class "Default")
      (node (ref "U6") (pin "4") (pinfunction "4_4") (pintype "passive"))
    )
    (net (code "100") (name "unconnected-(U6-Pad5)") (class "Default")
      (node (ref "U6") (pin "5") (pinfunction "5_5") (pintype "passive"))
    )
    (net (code "101") (name "unconnected-(U6-Pad6)") (class "Default")
      (node (ref "U6") (pin "6") (pinfunction "6_6") (pintype "passive"))
    )
    (net (code "102") (name "unconnected-(U6-Pad9)") (class "Default")
      (node (ref "U6") (pin "9") (pinfunction "9_9") (pintype "passive"))
    )
    (net (code "103") (name "unconnected-(U6-Pad10)") (class "Default")
      (node (ref "U6") (pin "10") (pinfunction "10_10") (pintype "passive"))
    )
    (net (code "104") (name "unconnected-(U6-Pad11)") (class "Default")
      (node (ref "U6") (pin "11") (pinfunction "11_11") (pintype "passive"))
    )
    (net (code "105") (name "unconnected-(U6-Pad12)") (class "Default")
      (node (ref "U6") (pin "12") (pinfunction "12_12") (pintype "passive"))
    )
    (net (code "106") (name "unconnected-(U6-Pad13)") (class "Default")
      (node (ref "U6") (pin "13") (pinfunction "13_13") (pintype "passive"))
    )
    (net (code "107") (name "unconnected-(USB1-CC1-PadA5)") (class "Default")
      (node (ref "USB1") (pin "A5") (pinfunction "CC1_A5") (pintype "passive"))
    )
    (net (code "108") (name "unconnected-(USB1-RX1+-PadB11)") (class "Default")
      (node (ref "USB1") (pin "B11") (pinfunction "RX1+_B11") (pintype "passive"))
    )
    (net (code "109") (name "unconnected-(USB1-RX1--PadB10)") (class "Default")
      (node (ref "USB1") (pin "B10") (pinfunction "RX1-_B10") (pintype "passive"))
    )
    (net (code "110") (name "unconnected-(USB1-RX2+-PadA11)") (class "Default")
      (node (ref "USB1") (pin "A11") (pinfunction "RX2+_A11") (pintype "passive"))
    )
    (net (code "111") (name "unconnected-(USB1-RX2--PadA10)") (class "Default")
      (node (ref "USB1") (pin "A10") (pinfunction "RX2-_A10") (pintype "passive"))
    )
    (net (code "112") (name "unconnected-(USB1-SBU1-PadA8)") (class "Default")
      (node (ref "USB1") (pin "A8") (pinfunction "SBU1_A8") (pintype "passive"))
    )
    (net (code "113") (name "unconnected-(USB1-SBU2-PadB8)") (class "Default")
      (node (ref "USB1") (pin "B8") (pinfunction "SBU2_B8") (pintype "passive"))
    )
    (net (code "114") (name "unconnected-(USB1-TX1+-PadA2)") (class "Default")
      (node (ref "USB1") (pin "A2") (pinfunction "TX1+_A2") (pintype "passive"))
    )
    (net (code "115") (name "unconnected-(USB1-TX1--PadA3)") (class "Default")
      (node (ref "USB1") (pin "A3") (pinfunction "TX1-_A3") (pintype "passive"))
    )
    (net (code "116") (name "unconnected-(USB1-TX2+-PadB2)") (class "Default")
      (node (ref "USB1") (pin "B2") (pinfunction "TX2+_B2") (pintype "passive"))
    )
    (net (code "117") (name "unconnected-(USB1-TX2--PadB3)") (class "Default")
      (node (ref "USB1") (pin "B3") (pinfunction "TX2-_B3") (pintype "passive"))
    )
  )
)
